# AudioAmp_V1.net
KiCad netlist of a schematic drawn in EAGLE
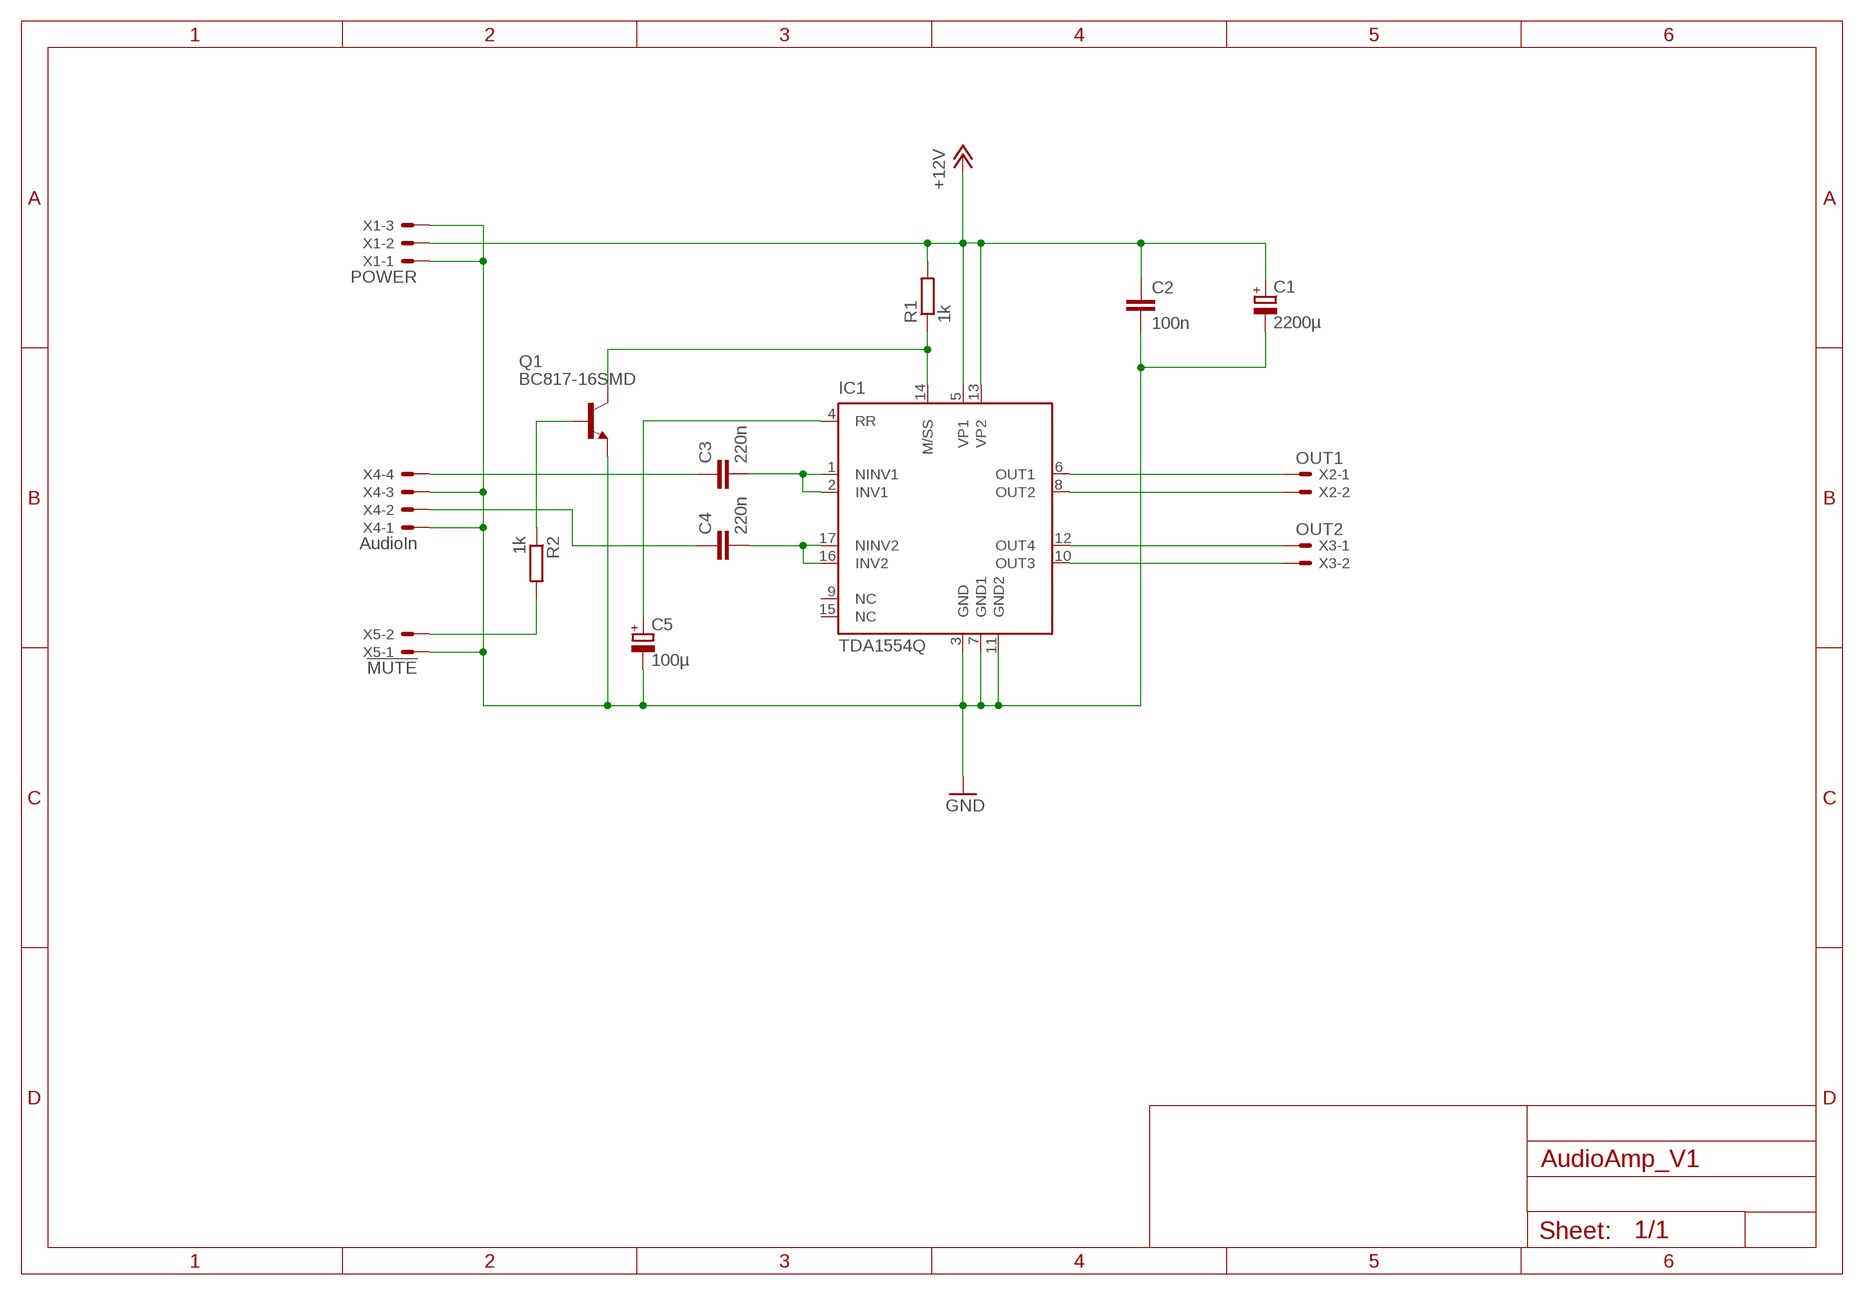
[diagram p0: schematic, sheet 1]

(export (version "E")
  (design (tool "Eeschema 10.0.6"))
  (components
    (comp (ref "C1")
      (value "2200µ")
      (footprint "eagle-import:E7,5-18")
      (libsource (lib "eagle-import") (part "CPOL-EUE7.5-18"))
    )
    (comp (ref "C2")
      (value "100n")
      (footprint "eagle-import:C050-025X075")
      (libsource (lib "eagle-import") (part "C-EU050-025X075"))
    )
    (comp (ref "C3")
      (value "220n")
      (footprint "eagle-import:C050-025X075")
      (libsource (lib "eagle-import") (part "C-EU050-025X075"))
    )
    (comp (ref "C4")
      (value "220n")
      (footprint "eagle-import:C050-025X075")
      (libsource (lib "eagle-import") (part "C-EU050-025X075"))
    )
    (comp (ref "C5")
      (value "100µ")
      (footprint "eagle-import:E2,5-7")
      (libsource (lib "eagle-import") (part "CPOL-EUE2.5-7"))
    )
    (comp (ref "IC1")
      (value "TDA1554Q")
      (footprint "eagle-import:MULTIWAT-SIL17")
      (libsource (lib "eagle-import") (part "TDA1554Q"))
    )
    (comp (ref "Q1")
      (value "BC817-16SMD")
      (footprint "eagle-import:SOT23-BEC")
      (libsource (lib "eagle-import") (part "BC817SMD-16"))
    )
    (comp (ref "R1")
      (value "1k")
      (footprint "eagle-import:0204_7")
      (libsource (lib "eagle-import") (part "R-EU_0204/7"))
    )
    (comp (ref "R2")
      (value "1k")
      (footprint "eagle-import:0204_7")
      (libsource (lib "eagle-import") (part "R-EU_0204/7"))
    )
    (comp (ref "X1")
      (value "POWER")
      (footprint "eagle-import:22-23-2031")
      (fields (field (name "MF") "MOLEX") (field (name "MPN") "22-23-2031"))
      (libsource (lib "eagle-import") (part "22-23-2031"))
    )
    (comp (ref "X2")
      (value "OUT1")
      (footprint "eagle-import:22-23-2021")
      (fields (field (name "MF") "MOLEX") (field (name "MPN") "22-23-2021"))
      (libsource (lib "eagle-import") (part "22-23-2021"))
    )
    (comp (ref "X3")
      (value "OUT2")
      (footprint "eagle-import:22-23-2021")
      (fields (field (name "MF") "MOLEX") (field (name "MPN") "22-23-2021"))
      (libsource (lib "eagle-import") (part "22-23-2021"))
    )
    (comp (ref "X4")
      (value "AudioIn")
      (footprint "eagle-import:22-23-2041")
      (fields (field (name "MF") "MOLEX") (field (name "MPN") "22-23-2041"))
      (libsource (lib "eagle-import") (part "22-23-2041"))
    )
    (comp (ref "X5")
      (value "!MUTE")
      (footprint "eagle-import:22-23-2021")
      (fields (field (name "MF") "MOLEX") (field (name "MPN") "22-23-2021"))
      (libsource (lib "eagle-import") (part "22-23-2021"))
    )
  )
  (nets
    (net (code "1") (name "+12V") (class "Default")
      (node (ref "C1") (pin "+") (pinfunction "+_+") (pintype "passive"))
      (node (ref "C2") (pin "1") (pinfunction "1_1") (pintype "passive"))
      (node (ref "IC1") (pin "13") (pinfunction "VP2_13") (pintype "power_in"))
      (node (ref "IC1") (pin "5") (pinfunction "VP1_5") (pintype "passive"))
      (node (ref "R1") (pin "2") (pinfunction "2_2") (pintype "passive"))
      (node (ref "X1") (pin "2") (pinfunction "S_2") (pintype "passive"))
    )
    (net (code "2") (name "GND") (class "Default")
      (node (ref "C1") (pin "-") (pinfunction "-_-") (pintype "passive"))
      (node (ref "C2") (pin "2") (pinfunction "2_2") (pintype "passive"))
      (node (ref "C5") (pin "-") (pinfunction "-_-") (pintype "passive"))
      (node (ref "IC1") (pin "11") (pinfunction "GND2_11") (pintype "power_in"))
      (node (ref "IC1") (pin "3") (pinfunction "GND_3") (pintype "passive"))
      (node (ref "IC1") (pin "7") (pinfunction "GND1_7") (pintype "power_in"))
      (node (ref "Q1") (pin "E") (pinfunction "E_E") (pintype "passive"))
      (node (ref "X1") (pin "1") (pinfunction "S_1") (pintype "passive"))
      (node (ref "X1") (pin "3") (pinfunction "S_3") (pintype "passive"))
      (node (ref "X4") (pin "1") (pinfunction "S_1") (pintype "passive"))
      (node (ref "X4") (pin "3") (pinfunction "S_3") (pintype "passive"))
      (node (ref "X5") (pin "1") (pinfunction "S_1") (pintype "passive"))
    )
    (net (code "3") (name "Net-(IC1-INV1)") (class "Default")
      (node (ref "C3") (pin "2") (pinfunction "2_2") (pintype "passive"))
      (node (ref "IC1") (pin "1") (pinfunction "NINV1_1") (pintype "input"))
      (node (ref "IC1") (pin "2") (pinfunction "INV1_2") (pintype "input"))
    )
    (net (code "4") (name "Net-(IC1-INV2)") (class "Default")
      (node (ref "C4") (pin "2") (pinfunction "2_2") (pintype "passive"))
      (node (ref "IC1") (pin "16") (pinfunction "INV2_16") (pintype "input"))
      (node (ref "IC1") (pin "17") (pinfunction "NINV2_17") (pintype "input"))
    )
    (net (code "5") (name "Net-(IC1-M{slash}SS)") (class "Default")
      (node (ref "IC1") (pin "14") (pinfunction "M/SS_14") (pintype "passive"))
      (node (ref "Q1") (pin "C") (pinfunction "C_C") (pintype "passive"))
      (node (ref "R1") (pin "1") (pinfunction "1_1") (pintype "passive"))
    )
    (net (code "6") (name "Net-(IC1-OUT1)") (class "Default")
      (node (ref "IC1") (pin "6") (pinfunction "OUT1_6") (pintype "output"))
      (node (ref "X2") (pin "1") (pinfunction "S_1") (pintype "passive"))
    )
    (net (code "7") (name "Net-(IC1-OUT2)") (class "Default")
      (node (ref "IC1") (pin "8") (pinfunction "OUT2_8") (pintype "output"))
      (node (ref "X2") (pin "2") (pinfunction "S_2") (pintype "passive"))
    )
    (net (code "8") (name "Net-(IC1-OUT3)") (class "Default")
      (node (ref "IC1") (pin "10") (pinfunction "OUT3_10") (pintype "output"))
      (node (ref "X3") (pin "2") (pinfunction "S_2") (pintype "passive"))
    )
    (net (code "9") (name "Net-(IC1-OUT4)") (class "Default")
      (node (ref "IC1") (pin "12") (pinfunction "OUT4_12") (pintype "output"))
      (node (ref "X3") (pin "1") (pinfunction "S_1") (pintype "passive"))
    )
    (net (code "10") (name "Net-(IC1-RR)") (class "Default")
      (node (ref "C5") (pin "+") (pinfunction "+_+") (pintype "passive"))
      (node (ref "IC1") (pin "4") (pinfunction "RR_4") (pintype "passive"))
    )
    (net (code "11") (name "Net-(Q1-PadB)") (class "Default")
      (node (ref "Q1") (pin "B") (pinfunction "B_B") (pintype "passive"))
      (node (ref "R2") (pin "1") (pinfunction "1_1") (pintype "passive"))
    )
    (net (code "12") (name "Net-(X4B-S)") (class "Default")
      (node (ref "C4") (pin "1") (pinfunction "1_1") (pintype "passive"))
      (node (ref "X4") (pin "2") (pinfunction "S_2") (pintype "passive"))
    )
    (net (code "13") (name "Net-(X4D-S)") (class "Default")
      (node (ref "C3") (pin "1") (pinfunction "1_1") (pintype "passive"))
      (node (ref "X4") (pin "4") (pinfunction "S_4") (pintype "passive"))
    )
    (net (code "14") (name "Net-(X5B-S)") (class "Default")
      (node (ref "R2") (pin "2") (pinfunction "2_2") (pintype "passive"))
      (node (ref "X5") (pin "2") (pinfunction "S_2") (pintype "passive"))
    )
    (net (code "15") (name "unconnected-(IC1-NC-Pad9)") (class "Default")
      (node (ref "IC1") (pin "9") (pinfunction "NC_9") (pintype "passive"))
    )
    (net (code "16") (name "unconnected-(IC1-NC-Pad15)") (class "Default")
      (node (ref "IC1") (pin "15") (pinfunction "NC_15") (pintype "passive"))
    )
  )
)
